# INTERFACE.net
KiCad netlist of a schematic drawn in Altium Designer
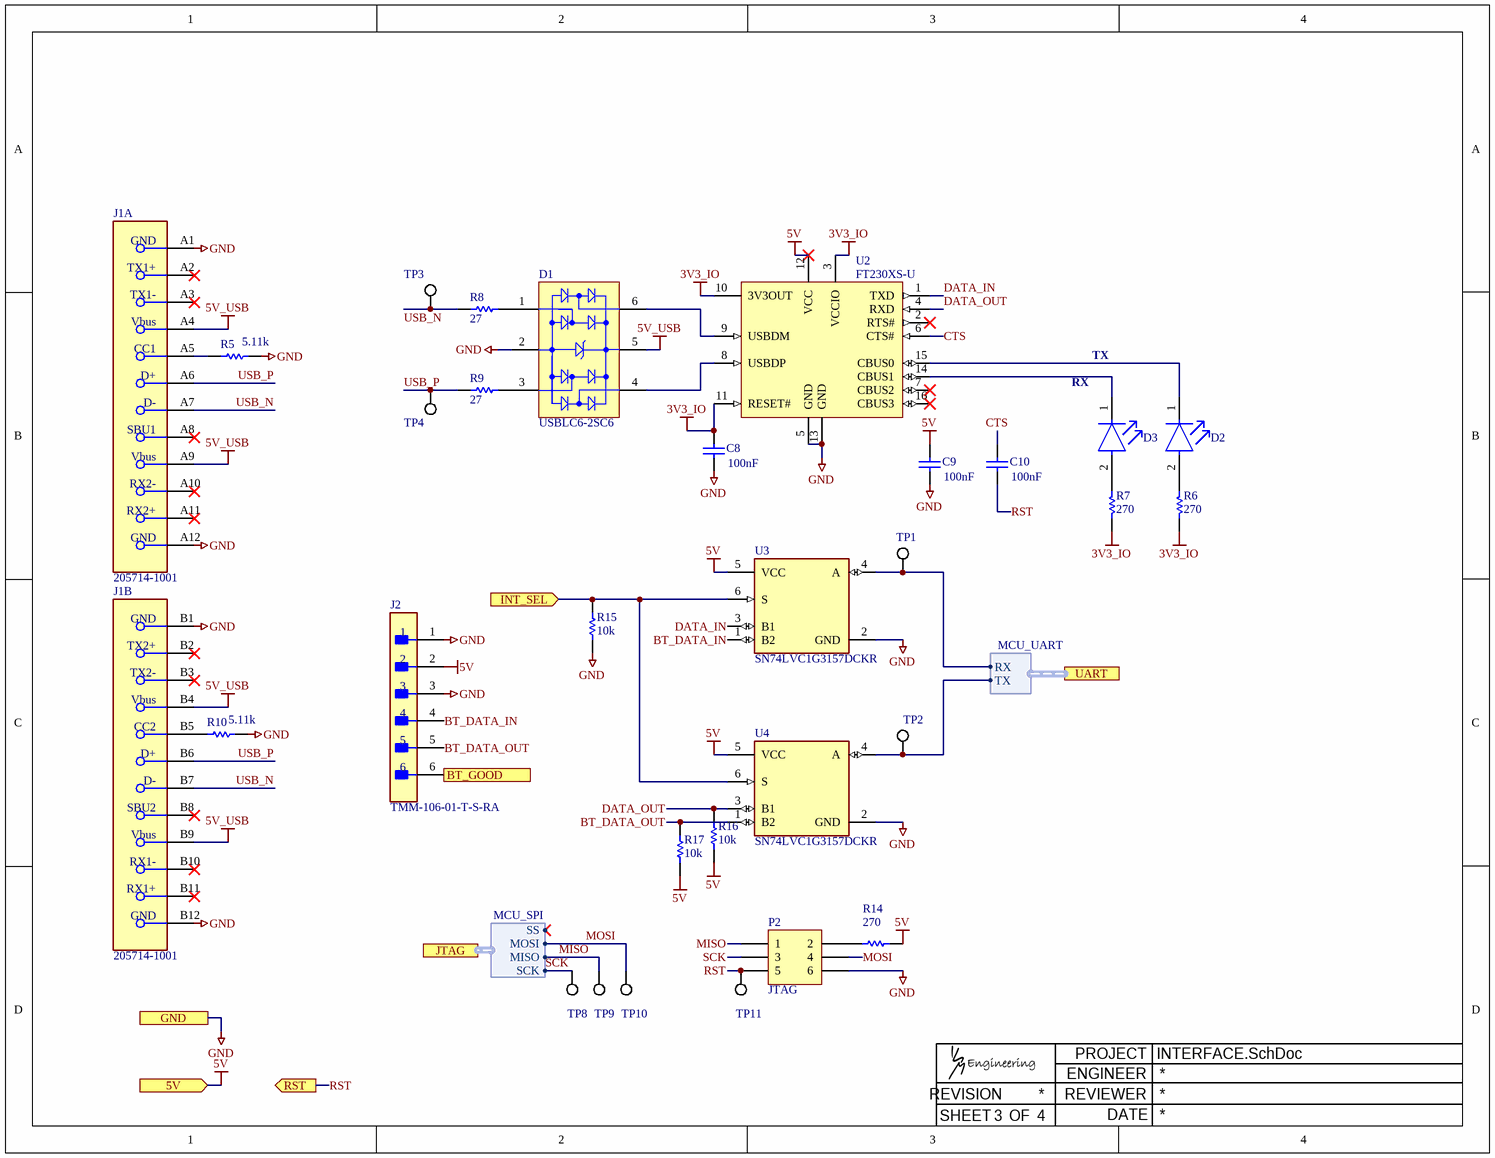
[diagram p0: INTERFACE.SchDoc]

(export (version "E")
  (design (tool "Eeschema 10.0.6"))
  (components
    (comp (ref "C8")
      (value "100nF")
      (footprint "CAPC1005X56X25ML10T15")
      (fields
        (field (name "MANUFACTURER") "AVX Interconnect / Elco")
        (field (name "PART NUMBER") "0402YG104ZAT2A")
      )
      (libsource (lib "Altium Content Vault") (part "CAP"))
    )
    (comp (ref "C9")
      (value "100nF")
      (footprint "CAPC1005X56X25ML10T15")
      (fields
        (field (name "MANUFACTURER") "AVX Interconnect / Elco")
        (field (name "PART NUMBER") "0402YG104ZAT2A")
      )
      (libsource (lib "Altium Content Vault") (part "CAP"))
    )
    (comp (ref "C10")
      (value "100nF")
      (footprint "CAPC1005X56X25ML10T15")
      (fields
        (field (name "MANUFACTURER") "AVX Interconnect / Elco")
        (field (name "PART NUMBER") "0402YG104ZAT2A")
      )
      (libsource (lib "Altium Content Vault") (part "CAP"))
    )
    (comp (ref "D1")
      (value "USBLC6-2SC6")
      (footprint "STM-SOT23-6L_V")
      (description "Very low capacitance ESD protection, 3.5 pF, -40 to 125 degC, 6-Pin SOT23, RoHS, Tape and Reel")
      (fields (field (name "MANUFACTURER") "STMicroelectronics"))
      (libsource (lib "Altium Content Vault") (part "STM-USB_DVI_HDMIULC6-4SC6X-SOT23-6L"))
    )
    (comp (ref "D2")
      (value "LTST-C190KGKT")
      (footprint "FP-LTST-C190KGKT-MFG")
      (description "LED GREEN CLEAR CHIP SMD")
      (libsource (lib "Altium Content Vault") (part "8706943c75ba83719d021d2fdc84c58"))
    )
    (comp (ref "D3")
      (value "LTST-C190KGKT")
      (footprint "FP-LTST-C190KGKT-MFG")
      (description "LED GREEN CLEAR CHIP SMD")
      (libsource (lib "Altium Content Vault") (part "8706943c75ba83719d021d2fdc84c58"))
    )
    (comp (ref "J1")
      (value "205714-1001")
      (footprint "FP-205714-1001-MFG")
      (description "USB TYPE C WITH SCREW HOLE  GM")
      (libsource (lib "Altium Content Vault") (part "1a8b11fb010c6447a7219bce639d1f1"))
    )
    (comp (ref "J2")
      (value "TMM-106-01-T-S-RA")
      (footprint "FP-TMM-106-01-T-S-RA-MFG")
      (description "CONN HEADER R/A 6POS 2MM")
      (libsource (lib "Altium Content Vault") (part "f2cb566baf1c37ab5a3b8e90bbeafd6"))
    )
    (comp (ref "P2")
      (value "MHDR2X3")
      (footprint "MHDR2X3")
      (description "Header, 3-Pin, Dual row")
      (fields (field (name "PUBLISHER") "Altium Limited"))
      (libsource (lib "Miscellaneous Connectors") (part "MHDR2X3"))
    )
    (comp (ref "R5")
      (value "5.11k")
      (footprint "RESC1005X40X25NL05T05")
      (fields (field (name "MANUFACTURER") "Panasonic") (field (name "PART NUMBER") "ERJ-2RKF5111X"))
      (libsource (lib "Altium Content Vault") (part "RES"))
    )
    (comp (ref "R6")
      (value "270")
      (footprint "RESC1005X40X25NL05T05")
      (fields (field (name "PART NUMBER") "ERJ2RKF2700X") (field (name "MANUFACTURER") "Panasonic"))
      (libsource (lib "Altium Content Vault") (part "RES"))
    )
    (comp (ref "R7")
      (value "270")
      (footprint "RESC1005X40X25NL05T05")
      (fields (field (name "PART NUMBER") "ERJ2RKF2700X") (field (name "MANUFACTURER") "Panasonic"))
      (libsource (lib "Altium Content Vault") (part "RES"))
    )
    (comp (ref "R8")
      (value "27")
      (footprint "RESC1005X40X25LL10T10")
      (fields (field (name "PART NUMBER") "RK73B1ETTP270J") (field (name "MANUFACTURER") "KOA Speer"))
      (libsource (lib "Altium Content Vault") (part "RES"))
    )
    (comp (ref "R9")
      (value "27")
      (footprint "RESC1005X40X25LL10T10")
      (fields (field (name "PART NUMBER") "RK73B1ETTP270J") (field (name "MANUFACTURER") "KOA Speer"))
      (libsource (lib "Altium Content Vault") (part "RES"))
    )
    (comp (ref "R10")
      (value "5.11k")
      (footprint "RESC1005X40X25NL05T05")
      (fields (field (name "MANUFACTURER") "Panasonic") (field (name "PART NUMBER") "ERJ-2RKF5111X"))
      (libsource (lib "Altium Content Vault") (part "RES"))
    )
    (comp (ref "R14")
      (value "270")
      (footprint "RESC1005X40X25NL05T05")
      (fields (field (name "PART NUMBER") "ERJ2RKF2700X") (field (name "MANUFACTURER") "Panasonic"))
      (libsource (lib "Altium Content Vault") (part "RES"))
    )
    (comp (ref "R15")
      (value "10k")
      (footprint "RESC1005X40X25LL05T05")
      (description "Chip Resistor, 10 KOhm, +/- 1%, 0.1 W, -55 to 155 degC, 0402 (1005 Metric), RoHS, Tape and Reel")
      (fields (field (name "TOLERANCE") "1%") (field (name "MANUFACTURER") "Panasonic"))
      (libsource (lib "Altium Content Vault") (part "RES-2"))
    )
    (comp (ref "R16")
      (value "10k")
      (footprint "RESC1005X40X25LL05T05")
      (description "Chip Resistor, 10 KOhm, +/- 1%, 0.1 W, -55 to 155 degC, 0402 (1005 Metric), RoHS, Tape and Reel")
      (fields (field (name "TOLERANCE") "1%") (field (name "MANUFACTURER") "Panasonic"))
      (libsource (lib "Altium Content Vault") (part "RES-2"))
    )
    (comp (ref "R17")
      (value "10k")
      (footprint "RESC1005X40X25LL05T05")
      (description "Chip Resistor, 10 KOhm, +/- 1%, 0.1 W, -55 to 155 degC, 0402 (1005 Metric), RoHS, Tape and Reel")
      (fields (field (name "TOLERANCE") "1%") (field (name "MANUFACTURER") "Panasonic"))
      (libsource (lib "Altium Content Vault") (part "RES-2"))
    )
    (comp (ref "TP1")
      (value "5019")
      (footprint "KSTN-5019_V")
      (description "Test Point, 1 Position SMD, RoHS, Tape and Reel")
      (libsource (lib "Altium Content Vault") (part "TESTPOINT_WHITE"))
    )
    (comp (ref "TP2")
      (value "5019")
      (footprint "KSTN-5019_V")
      (description "Test Point, 1 Position SMD, RoHS, Tape and Reel")
      (libsource (lib "Altium Content Vault") (part "TESTPOINT_WHITE"))
    )
    (comp (ref "TP3")
      (value "5019")
      (footprint "KSTN-5019_V")
      (description "Test Point, 1 Position SMD, RoHS, Tape and Reel")
      (libsource (lib "Altium Content Vault") (part "TESTPOINT_WHITE"))
    )
    (comp (ref "TP4")
      (value "5019")
      (footprint "KSTN-5019_V")
      (description "Test Point, 1 Position SMD, RoHS, Tape and Reel")
      (libsource (lib "Altium Content Vault") (part "TESTPOINT_WHITE"))
    )
    (comp (ref "TP8")
      (value "5019")
      (footprint "KSTN-5019_V")
      (description "Test Point, 1 Position SMD, RoHS, Tape and Reel")
      (libsource (lib "Altium Content Vault") (part "TESTPOINT_WHITE"))
    )
    (comp (ref "TP9")
      (value "5019")
      (footprint "KSTN-5019_V")
      (description "Test Point, 1 Position SMD, RoHS, Tape and Reel")
      (libsource (lib "Altium Content Vault") (part "TESTPOINT_WHITE"))
    )
    (comp (ref "TP10")
      (value "5019")
      (footprint "KSTN-5019_V")
      (description "Test Point, 1 Position SMD, RoHS, Tape and Reel")
      (libsource (lib "Altium Content Vault") (part "TESTPOINT_WHITE"))
    )
    (comp (ref "TP11")
      (value "5019")
      (footprint "KSTN-5019_V")
      (description "Test Point, 1 Position SMD, RoHS, Tape and Reel")
      (libsource (lib "Altium Content Vault") (part "TESTPOINT_WHITE"))
    )
    (comp (ref "U2")
      (value "FT230XS-U")
      (footprint "SSOP-16_N")
      (fields (field (name "MANUFACTURER") "FTDI"))
      (libsource (lib "Altium Content Vault") (part "COM-USB-FT230XS-IL16"))
    )
    (comp (ref "U3")
      (value "SN74LVC1G3157DCKR")
      (footprint "FP-DCK0006A-IPC_B")
      (description "IC SWITCH SPDT SC70-6")
      (libsource (lib "Altium Content Vault") (part "0261a57985ab8eeec66806cf7caee19"))
    )
    (comp (ref "U4")
      (value "SN74LVC1G3157DCKR")
      (footprint "FP-DCK0006A-IPC_B")
      (description "IC SWITCH SPDT SC70-6")
      (libsource (lib "Altium Content Vault") (part "0261a57985ab8eeec66806cf7caee19"))
    )
  )
  (nets
    (net (code "3") (name "/BT_DATA_IN") (class "Default")
      (node (ref "J2") (pin "4") (pinfunction "4_4") (pintype "passive"))
      (node (ref "U3") (pin "1") (pinfunction "B2_1") (pintype "bidirectional"))
    )
    (net (code "4") (name "/BT_DATA_OUT") (class "Default")
      (node (ref "J2") (pin "5") (pinfunction "5_5") (pintype "passive"))
      (node (ref "R17") (pin "2") (pinfunction "2_2") (pintype "passive"))
      (node (ref "U4") (pin "1") (pinfunction "B2_1") (pintype "bidirectional"))
    )
    (net (code "5") (name "/BT_GOOD") (class "Default")
      (node (ref "J2") (pin "6") (pinfunction "6_6") (pintype "passive"))
    )
    (net (code "6") (name "/CTS") (class "Default")
      (node (ref "C10") (pin "2") (pinfunction "2_2") (pintype "passive"))
      (node (ref "U2") (pin "6") (pinfunction "CTS#_6") (pintype "input"))
    )
    (net (code "7") (name "/DATA_IN") (class "Default")
      (node (ref "U2") (pin "1") (pinfunction "TXD_1") (pintype "output"))
      (node (ref "U3") (pin "3") (pinfunction "B1_3") (pintype "bidirectional"))
    )
    (net (code "8") (name "/DATA_OUT") (class "Default")
      (node (ref "R16") (pin "2") (pinfunction "2_2") (pintype "passive"))
      (node (ref "U2") (pin "4") (pinfunction "RXD_4") (pintype "input"))
      (node (ref "U4") (pin "3") (pinfunction "B1_3") (pintype "bidirectional"))
    )
    (net (code "9") (name "/INT_SEL") (class "Default")
      (node (ref "R15") (pin "1") (pinfunction "1_1") (pintype "passive"))
      (node (ref "U3") (pin "6") (pinfunction "S_6") (pintype "input"))
      (node (ref "U4") (pin "6") (pinfunction "S_6") (pintype "input"))
    )
    (net (code "10") (name "/MISO") (class "Default")
      (node (ref "P2") (pin "1") (pinfunction "1_1") (pintype "passive"))
      (node (ref "TP9") (pin "1") (pinfunction "1_1") (pintype "passive"))
    )
    (net (code "11") (name "/MOSI") (class "Default")
      (node (ref "P2") (pin "4") (pinfunction "4_4") (pintype "passive"))
      (node (ref "TP10") (pin "1") (pinfunction "1_1") (pintype "passive"))
    )
    (net (code "12") (name "/RST") (class "Default")
      (node (ref "C10") (pin "1") (pinfunction "1_1") (pintype "passive"))
      (node (ref "P2") (pin "5") (pinfunction "5_5") (pintype "passive"))
      (node (ref "TP11") (pin "1") (pinfunction "1_1") (pintype "passive"))
    )
    (net (code "13") (name "/RX") (class "Default")
      (node (ref "TP1") (pin "1") (pinfunction "1_1") (pintype "passive"))
      (node (ref "U3") (pin "4") (pinfunction "A_4") (pintype "bidirectional"))
    )
    (net (code "14") (name "/SCK") (class "Default")
      (node (ref "P2") (pin "3") (pinfunction "3_3") (pintype "passive"))
      (node (ref "TP8") (pin "1") (pinfunction "1_1") (pintype "passive"))
    )
    (net (code "15") (name "/TX") (class "Default")
      (node (ref "TP2") (pin "1") (pinfunction "1_1") (pintype "passive"))
      (node (ref "U4") (pin "4") (pinfunction "A_4") (pintype "bidirectional"))
    )
    (net (code "16") (name "/USB_N") (class "Default")
      (node (ref "J1") (pin "A7") (pinfunction "D-_A7") (pintype "passive"))
      (node (ref "J1") (pin "B7") (pinfunction "D-_B7") (pintype "passive"))
      (node (ref "R8") (pin "1") (pinfunction "1_1") (pintype "passive"))
      (node (ref "TP3") (pin "1") (pinfunction "1_1") (pintype "passive"))
    )
    (net (code "17") (name "/USB_P") (class "Default")
      (node (ref "J1") (pin "A6") (pinfunction "D+_A6") (pintype "passive"))
      (node (ref "J1") (pin "B6") (pinfunction "D+_B6") (pintype "passive"))
      (node (ref "R9") (pin "1") (pinfunction "1_1") (pintype "passive"))
      (node (ref "TP4") (pin "1") (pinfunction "1_1") (pintype "passive"))
    )
    (net (code "20") (name "3V3_IO") (class "Default")
      (node (ref "C8") (pin "2") (pinfunction "2_2") (pintype "passive"))
      (node (ref "R6") (pin "2") (pinfunction "2_2") (pintype "passive"))
      (node (ref "R7") (pin "2") (pinfunction "2_2") (pintype "passive"))
      (node (ref "U2") (pin "10") (pinfunction "3V3OUT_10") (pintype "power_in"))
      (node (ref "U2") (pin "11") (pinfunction "RESET#_11") (pintype "input"))
      (node (ref "U2") (pin "3") (pinfunction "VCCIO_3") (pintype "power_in"))
    )
    (net (code "21") (name "5V") (class "Default")
      (node (ref "C9") (pin "2") (pinfunction "2_2") (pintype "passive"))
      (node (ref "J2") (pin "2") (pinfunction "2_2") (pintype "passive"))
      (node (ref "R14") (pin "1") (pinfunction "1_1") (pintype "passive"))
      (node (ref "R16") (pin "1") (pinfunction "1_1") (pintype "passive"))
      (node (ref "R17") (pin "1") (pinfunction "1_1") (pintype "passive"))
      (node (ref "U2") (pin "12") (pinfunction "VCC_12") (pintype "power_in"))
      (node (ref "U3") (pin "5") (pinfunction "VCC_5") (pintype "power_in"))
      (node (ref "U4") (pin "5") (pinfunction "VCC_5") (pintype "power_in"))
    )
    (net (code "22") (name "5V_USB") (class "Default")
      (node (ref "D1") (pin "5") (pinfunction "VBUS_5") (pintype "passive"))
      (node (ref "J1") (pin "A4") (pinfunction "Vbus_A4") (pintype "passive"))
      (node (ref "J1") (pin "A9") (pinfunction "Vbus_A9") (pintype "passive"))
      (node (ref "J1") (pin "B4") (pinfunction "Vbus_B4") (pintype "passive"))
      (node (ref "J1") (pin "B9") (pinfunction "Vbus_B9") (pintype "passive"))
    )
    (net (code "23") (name "GND") (class "Default")
      (node (ref "C8") (pin "1") (pinfunction "1_1") (pintype "passive"))
      (node (ref "C9") (pin "1") (pinfunction "1_1") (pintype "passive"))
      (node (ref "D1") (pin "2") (pinfunction "GND_2") (pintype "passive"))
      (node (ref "J1") (pin "A1") (pinfunction "GND_A1") (pintype "passive"))
      (node (ref "J1") (pin "A12") (pinfunction "GND_A12") (pintype "passive"))
      (node (ref "J1") (pin "B1") (pinfunction "GND_B1") (pintype "passive"))
      (node (ref "J1") (pin "B12") (pinfunction "GND_B12") (pintype "passive"))
      (node (ref "J2") (pin "1") (pinfunction "1_1") (pintype "passive"))
      (node (ref "J2") (pin "3") (pinfunction "3_3") (pintype "passive"))
      (node (ref "P2") (pin "6") (pinfunction "6_6") (pintype "passive"))
      (node (ref "R10") (pin "1") (pinfunction "1_1") (pintype "passive"))
      (node (ref "R15") (pin "2") (pinfunction "2_2") (pintype "passive"))
      (node (ref "R5") (pin "1") (pinfunction "1_1") (pintype "passive"))
      (node (ref "U2") (pin "13") (pinfunction "GND_13") (pintype "power_in"))
      (node (ref "U2") (pin "5") (pinfunction "GND_5") (pintype "power_in"))
      (node (ref "U3") (pin "2") (pinfunction "GND_2") (pintype "power_in"))
      (node (ref "U4") (pin "2") (pinfunction "GND_2") (pintype "power_in"))
    )
    (net (code "24") (name "Net-(D1-I{slash}O_1)") (class "Default")
      (node (ref "D1") (pin "1") (pinfunction "I/O_1_1") (pintype "passive"))
      (node (ref "R8") (pin "2") (pinfunction "2_2") (pintype "passive"))
    )
    (net (code "25") (name "Net-(D1-I{slash}O_2)") (class "Default")
      (node (ref "D1") (pin "3") (pinfunction "I/O_2_3") (pintype "passive"))
      (node (ref "R9") (pin "2") (pinfunction "2_2") (pintype "passive"))
    )
    (net (code "26") (name "Net-(D1-I{slash}O_3)") (class "Default")
      (node (ref "D1") (pin "4") (pinfunction "I/O_3_4") (pintype "passive"))
      (node (ref "U2") (pin "8") (pinfunction "USBDP_8") (pintype "input"))
    )
    (net (code "27") (name "Net-(D1-I{slash}O_4)") (class "Default")
      (node (ref "D1") (pin "6") (pinfunction "I/O_4_6") (pintype "passive"))
      (node (ref "U2") (pin "9") (pinfunction "USBDM_9") (pintype "input"))
    )
    (net (code "28") (name "Net-(D2-A)") (class "Default")
      (node (ref "D2") (pin "2") (pinfunction "A_2") (pintype "passive"))
      (node (ref "R6") (pin "1") (pinfunction "1_1") (pintype "passive"))
    )
    (net (code "29") (name "Net-(D2-C)") (class "Default")
      (node (ref "D2") (pin "1") (pinfunction "C_1") (pintype "passive"))
      (node (ref "U2") (pin "15") (pinfunction "CBUS0_15") (pintype "bidirectional"))
    )
    (net (code "30") (name "Net-(D3-A)") (class "Default")
      (node (ref "D3") (pin "2") (pinfunction "A_2") (pintype "passive"))
      (node (ref "R7") (pin "1") (pinfunction "1_1") (pintype "passive"))
    )
    (net (code "31") (name "Net-(D3-C)") (class "Default")
      (node (ref "D3") (pin "1") (pinfunction "C_1") (pintype "passive"))
      (node (ref "U2") (pin "14") (pinfunction "CBUS1_14") (pintype "bidirectional"))
    )
    (net (code "32") (name "Net-(J1A-CC1)") (class "Default")
      (node (ref "J1") (pin "A5") (pinfunction "CC1_A5") (pintype "passive"))
      (node (ref "R5") (pin "2") (pinfunction "2_2") (pintype "passive"))
    )
    (net (code "33") (name "Net-(J1B-CC2)") (class "Default")
      (node (ref "J1") (pin "B5") (pinfunction "CC2_B5") (pintype "passive"))
      (node (ref "R10") (pin "2") (pinfunction "2_2") (pintype "passive"))
    )
    (net (code "34") (name "Net-(P2-Pad2)") (class "Default")
      (node (ref "P2") (pin "2") (pinfunction "2_2") (pintype "passive"))
      (node (ref "R14") (pin "2") (pinfunction "2_2") (pintype "passive"))
    )
    (net (code "35") (name "unconnected-(J1A-RX2+-PadA11)") (class "Default")
      (node (ref "J1") (pin "A11") (pinfunction "RX2+_A11") (pintype "passive+no_connect"))
    )
    (net (code "36") (name "unconnected-(J1A-RX2--PadA10)") (class "Default")
      (node (ref "J1") (pin "A10") (pinfunction "RX2-_A10") (pintype "passive+no_connect"))
    )
    (net (code "37") (name "unconnected-(J1A-SBU1-PadA8)") (class "Default")
      (node (ref "J1") (pin "A8") (pinfunction "SBU1_A8") (pintype "passive+no_connect"))
    )
    (net (code "38") (name "unconnected-(J1A-TX1+-PadA2)") (class "Default")
      (node (ref "J1") (pin "A2") (pinfunction "TX1+_A2") (pintype "passive+no_connect"))
    )
    (net (code "39") (name "unconnected-(J1A-TX1--PadA3)") (class "Default")
      (node (ref "J1") (pin "A3") (pinfunction "TX1-_A3") (pintype "passive+no_connect"))
    )
    (net (code "40") (name "unconnected-(J1B-RX1+-PadB11)") (class "Default")
      (node (ref "J1") (pin "B11") (pinfunction "RX1+_B11") (pintype "passive+no_connect"))
    )
    (net (code "41") (name "unconnected-(J1B-RX1--PadB10)") (class "Default")
      (node (ref "J1") (pin "B10") (pinfunction "RX1-_B10") (pintype "passive+no_connect"))
    )
    (net (code "42") (name "unconnected-(J1B-SBU2-PadB8)") (class "Default")
      (node (ref "J1") (pin "B8") (pinfunction "SBU2_B8") (pintype "passive+no_connect"))
    )
    (net (code "43") (name "unconnected-(J1B-TX2+-PadB2)") (class "Default")
      (node (ref "J1") (pin "B2") (pinfunction "TX2+_B2") (pintype "passive+no_connect"))
    )
    (net (code "44") (name "unconnected-(J1B-TX2--PadB3)") (class "Default")
      (node (ref "J1") (pin "B3") (pinfunction "TX2-_B3") (pintype "passive+no_connect"))
    )
    (net (code "45") (name "unconnected-(U2-CBUS2-Pad7)") (class "Default")
      (node (ref "U2") (pin "7") (pinfunction "CBUS2_7") (pintype "bidirectional+no_connect"))
    )
    (net (code "46") (name "unconnected-(U2-CBUS3-Pad16)") (class "Default")
      (node (ref "U2") (pin "16") (pinfunction "CBUS3_16") (pintype "bidirectional+no_connect"))
    )
    (net (code "47") (name "unconnected-(U2-RTS#-Pad2)") (class "Default")
      (node (ref "U2") (pin "2") (pinfunction "RTS#_2") (pintype "output+no_connect"))
    )
  )
)
